# Debug.net
KiCad netlist of a schematic drawn in Altium Designer
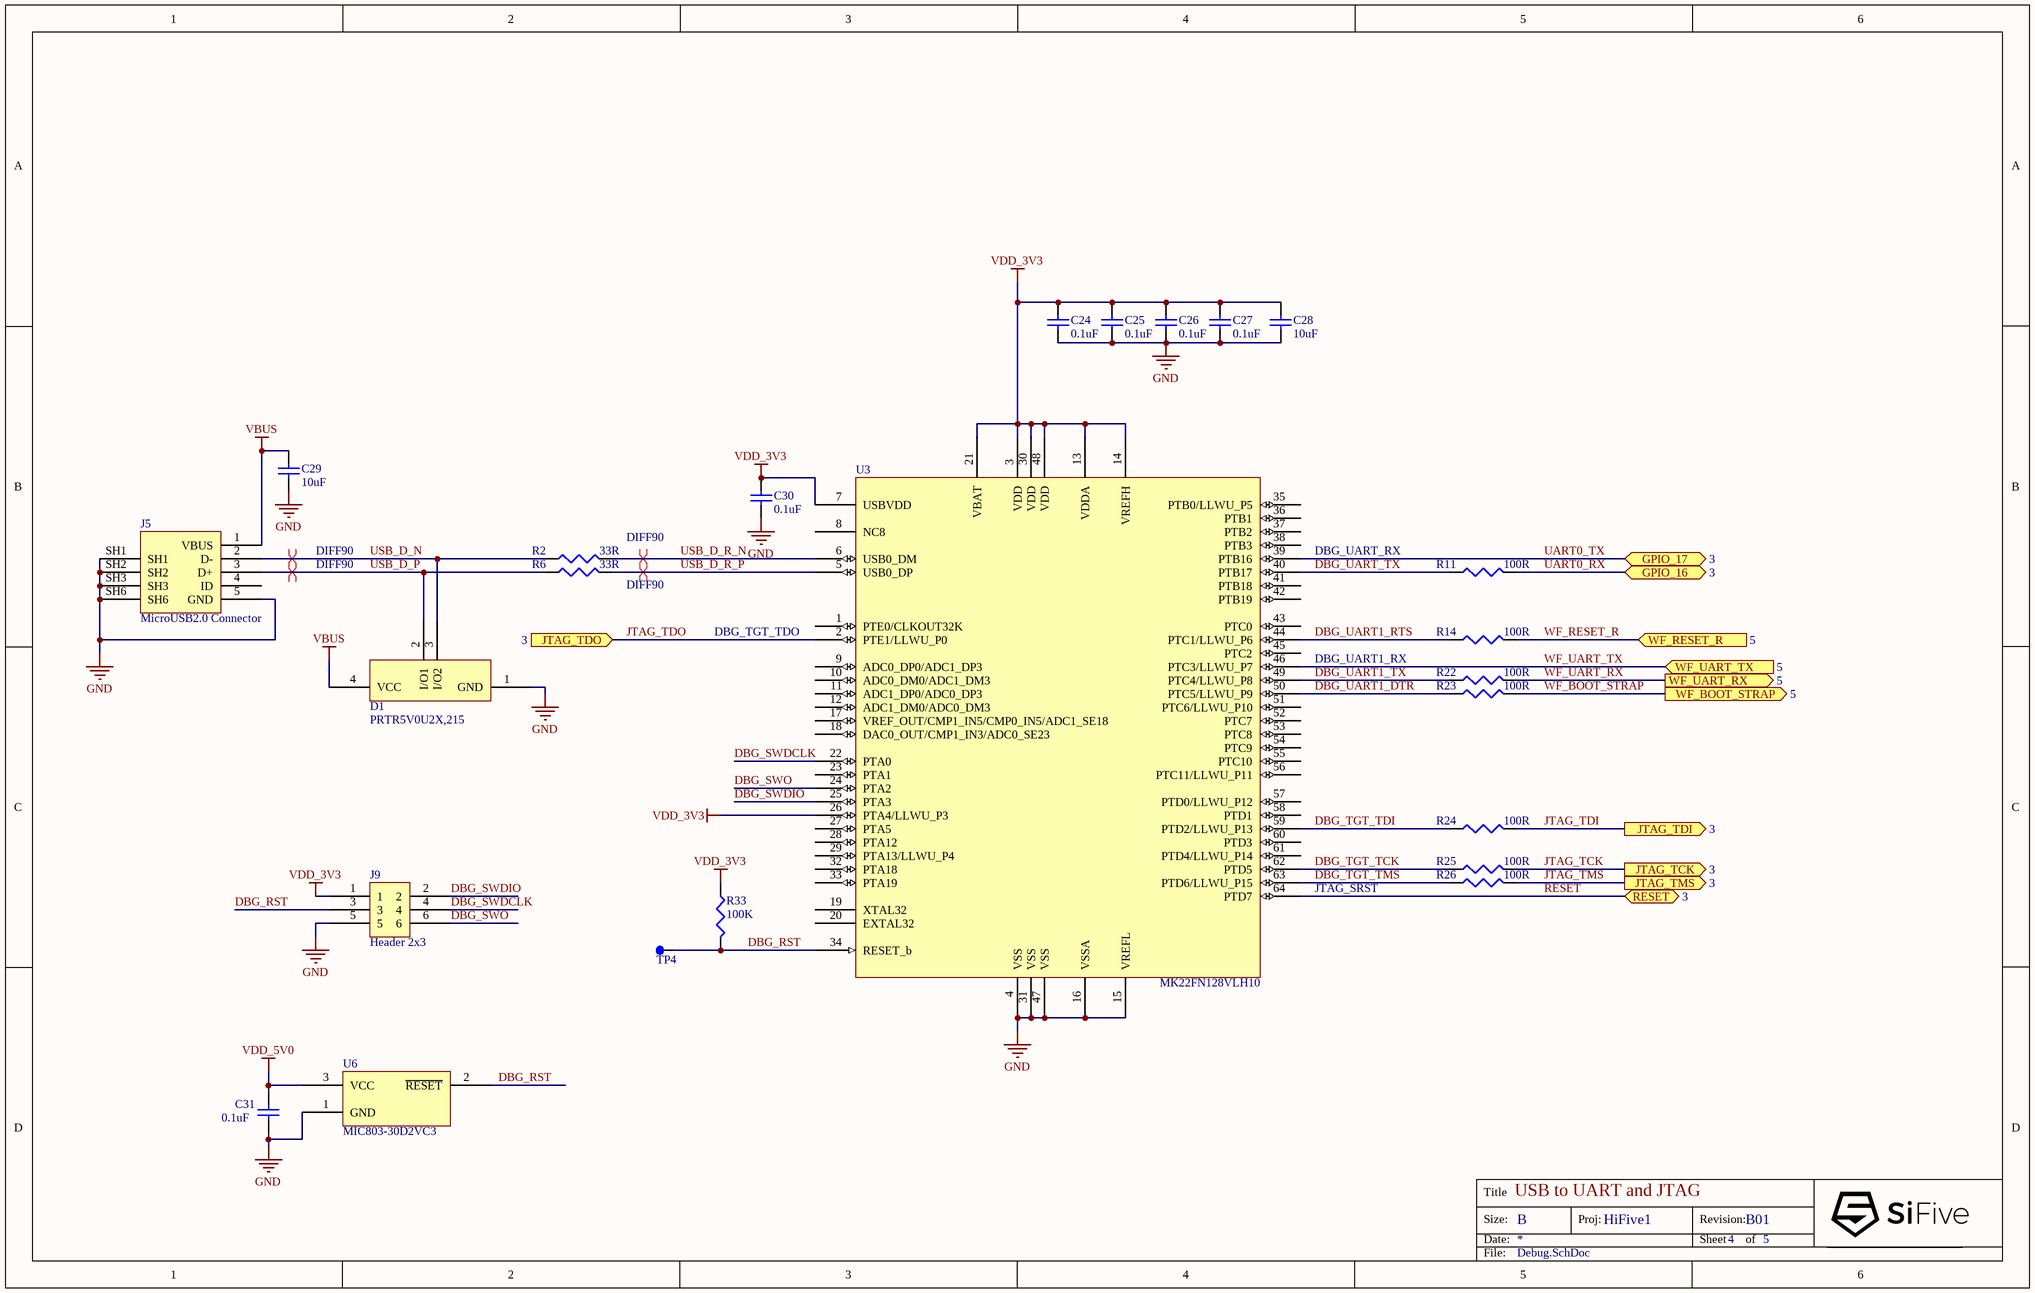
[diagram p0: Debug.SchDoc]

(export (version "E")
  (design (tool "Eeschema 10.0.6"))
  (components
    (comp (ref "C24")
      (value "0.1uF")
      (footprint "C0402")
      (description "0.10µF 16V Ceramic Capacitor X7R 0402")
      (fields
        (field (name "PART NUMBER") "C0100004")
        (field (name "MANUFACTURER") "Samsung Electro-Mechanics")
      )
      (libsource (lib "PartLibrary") (part "Capacitor - non polarized"))
    )
    (comp (ref "C25")
      (value "0.1uF")
      (footprint "C0402")
      (description "0.10µF 16V Ceramic Capacitor X7R 0402")
      (fields
        (field (name "PART NUMBER") "C0100004")
        (field (name "MANUFACTURER") "Samsung Electro-Mechanics")
      )
      (libsource (lib "PartLibrary") (part "Capacitor - non polarized"))
    )
    (comp (ref "C26")
      (value "0.1uF")
      (footprint "C0402")
      (description "0.10µF 16V Ceramic Capacitor X7R 0402")
      (fields
        (field (name "PART NUMBER") "C0100004")
        (field (name "MANUFACTURER") "Samsung Electro-Mechanics")
      )
      (libsource (lib "PartLibrary") (part "Capacitor - non polarized"))
    )
    (comp (ref "C27")
      (value "0.1uF")
      (footprint "C0402")
      (description "0.10µF 16V Ceramic Capacitor X7R 0402")
      (fields
        (field (name "PART NUMBER") "C0100004")
        (field (name "MANUFACTURER") "Samsung Electro-Mechanics")
      )
      (libsource (lib "PartLibrary") (part "Capacitor - non polarized"))
    )
    (comp (ref "C28")
      (value "10uF")
      (footprint "C0603")
      (description "CAP CER 10UF 10V X5R 0603")
      (fields (field (name "PART NUMBER") "C0100033") (field (name "MANUFACTURER") "Murata Electronics"))
      (libsource (lib "PartLibrary") (part "Capacitor - non polarized"))
    )
    (comp (ref "C29")
      (value "10uF")
      (footprint "C0603")
      (description "CAP CER 10UF 10V X5R 0603")
      (fields (field (name "PART NUMBER") "C0100033") (field (name "MANUFACTURER") "Murata Electronics"))
      (libsource (lib "PartLibrary") (part "Capacitor - non polarized"))
    )
    (comp (ref "C30")
      (value "0.1uF")
      (footprint "C0402")
      (description "0.10µF 16V Ceramic Capacitor X7R 0402")
      (fields
        (field (name "PART NUMBER") "C0100004")
        (field (name "MANUFACTURER") "Samsung Electro-Mechanics")
      )
      (libsource (lib "PartLibrary") (part "Capacitor - non polarized"))
    )
    (comp (ref "C31")
      (value "0.1uF")
      (footprint "C0402")
      (description "0.10µF 16V Ceramic Capacitor X7R 0402")
      (fields
        (field (name "PART NUMBER") "C0100004")
        (field (name "MANUFACTURER") "Samsung Electro-Mechanics")
      )
      (libsource (lib "PartLibrary") (part "Capacitor - non polarized"))
    )
    (comp (ref "D1")
      (value "PRTR5V0U2X,215")
      (footprint "SOT-143B")
      (description "TVS DIODE 5.5V SOT143B")
      (fields (field (name "PART NUMBER") "D0000012") (field (name "MANUFACTURER") "Nexperia"))
      (libsource (lib "PartLibrary") (part "PRTR5V0U2X_ESDDIODE"))
    )
    (comp (ref "J5")
      (value "MicroUSB2.0 Connector")
      (footprint "FCI_10118194-0001LF")
      (description "USB - micro B USB 2.0 Receptacle Connector 5 Position Surface Mount, Right Angle, Horizontal")
      (fields (field (name "PART NUMBER") "J0000048") (field (name "MANUFACTURER") "Amphenol FCI"))
      (libsource (lib "PartLibrary") (part "MicroUSB2.0 Connector"))
    )
    (comp (ref "J9")
      (value "Header 2x3")
      (footprint "TC2030-IDC-FP")
      (description "2x3 Connector, Small footprint, no legs, no component")
      (fields (field (name "PART NUMBER") "J0000045") (field (name "MANUFACTURER") "Tag Connect"))
      (libsource (lib "PartLibrary") (part "Header 2x3"))
    )
    (comp (ref "R2")
      (value "33R")
      (footprint "R0402")
      (description "RES SMD 33 OHM 1% 1/16W 0402")
      (fields (field (name "PART NUMBER") "R0000044") (field (name "MANUFACTURER") "Yageo"))
      (libsource (lib "PartLibrary") (part "Resistor"))
    )
    (comp (ref "R6")
      (value "33R")
      (footprint "R0402")
      (description "RES SMD 33 OHM 1% 1/16W 0402")
      (fields (field (name "PART NUMBER") "R0000044") (field (name "MANUFACTURER") "Yageo"))
      (libsource (lib "PartLibrary") (part "Resistor"))
    )
    (comp (ref "R11")
      (value "100R")
      (footprint "R0402")
      (description "RES SMD 100 OHM 1% 1/16W 0402")
      (fields (field (name "PART NUMBER") "R0000020") (field (name "MANUFACTURER") "Yageo"))
      (libsource (lib "PartLibrary") (part "Resistor"))
    )
    (comp (ref "R14")
      (value "100R")
      (footprint "R0402")
      (description "RES SMD 100 OHM 1% 1/16W 0402")
      (fields (field (name "PART NUMBER") "R0000020") (field (name "MANUFACTURER") "Yageo"))
      (libsource (lib "PartLibrary") (part "Resistor"))
    )
    (comp (ref "R22")
      (value "100R")
      (footprint "R0402")
      (description "RES SMD 100 OHM 1% 1/16W 0402")
      (fields (field (name "PART NUMBER") "R0000020") (field (name "MANUFACTURER") "Yageo"))
      (libsource (lib "PartLibrary") (part "Resistor"))
    )
    (comp (ref "R23")
      (value "100R")
      (footprint "R0402")
      (description "RES SMD 100 OHM 1% 1/16W 0402")
      (fields (field (name "PART NUMBER") "R0000020") (field (name "MANUFACTURER") "Yageo"))
      (libsource (lib "PartLibrary") (part "Resistor"))
    )
    (comp (ref "R24")
      (value "100R")
      (footprint "R0402")
      (description "RES SMD 100 OHM 1% 1/16W 0402")
      (fields (field (name "PART NUMBER") "R0000020") (field (name "MANUFACTURER") "Yageo"))
      (libsource (lib "PartLibrary") (part "Resistor"))
    )
    (comp (ref "R25")
      (value "100R")
      (footprint "R0402")
      (description "RES SMD 100 OHM 1% 1/16W 0402")
      (fields (field (name "PART NUMBER") "R0000020") (field (name "MANUFACTURER") "Yageo"))
      (libsource (lib "PartLibrary") (part "Resistor"))
    )
    (comp (ref "R26")
      (value "100R")
      (footprint "R0402")
      (description "RES SMD 100 OHM 1% 1/16W 0402")
      (fields (field (name "PART NUMBER") "R0000020") (field (name "MANUFACTURER") "Yageo"))
      (libsource (lib "PartLibrary") (part "Resistor"))
    )
    (comp (ref "R33")
      (value "100K")
      (footprint "R0402")
      (description "RES SMD 100K OHM 1% 1/16W 0402")
      (fields (field (name "PART NUMBER") "R0000012") (field (name "MANUFACTURER") "Yageo"))
      (libsource (lib "PartLibrary") (part "Resistor"))
    )
    (comp (ref "TP4")
      (value "Testpoint")
      (footprint "Testpoint_SMT")
      (description "Test Point SMT")
      (fields (field (name "PART NUMBER") "M0000002"))
      (libsource (lib "PartLibrary") (part "Testpoint"))
    )
    (comp (ref "U3")
      (value "MK22FN128VLH10")
      (footprint "LQFP-64")
      (fields (field (name "PART NUMBER") "U0000058") (field (name "MANUFACTURER") "NXP USA Inc"))
      (libsource (lib "PartLibrary") (part "MK22FN128VLH10"))
    )
    (comp (ref "U6")
      (value "MIC803-30D2VC3")
      (footprint "SOT65P210X110-3N_A")
      (description "IC MPU SUPERVISOR SC70-3")
      (fields (field (name "PART NUMBER") "U0000076") (field (name "MANUFACTURER") "Microchip"))
      (libsource (lib "PartLibrary") (part "MIC803-30D2VC3"))
    )
  )
  (nets
    (net (code "1") (name "/DBG_RST") (class "Default")
      (node (ref "J9") (pin "3") (pinfunction "3_3") (pintype "passive"))
      (node (ref "R33") (pin "2") (pinfunction "2_2") (pintype "passive"))
      (node (ref "TP4") (pin "1") (pinfunction "1_1") (pintype "passive"))
      (node (ref "U3") (pin "34") (pinfunction "RESET_b_34") (pintype "input"))
      (node (ref "U6") (pin "2") (pinfunction "~{RESET}_2") (pintype "open_collector"))
    )
    (net (code "2") (name "/DBG_SWDCLK") (class "Default")
      (node (ref "J9") (pin "4") (pinfunction "4_4") (pintype "passive"))
      (node (ref "U3") (pin "22") (pinfunction "PTA0_22") (pintype "bidirectional"))
    )
    (net (code "3") (name "/DBG_SWDIO") (class "Default")
      (node (ref "J9") (pin "2") (pinfunction "2_2") (pintype "passive"))
      (node (ref "U3") (pin "25") (pinfunction "PTA3_25") (pintype "bidirectional"))
    )
    (net (code "4") (name "/DBG_SWO") (class "Default")
      (node (ref "J9") (pin "6") (pinfunction "6_6") (pintype "passive"))
      (node (ref "U3") (pin "24") (pinfunction "PTA2_24") (pintype "bidirectional"))
    )
    (net (code "5") (name "/DBG_TGT_TCK") (class "Default")
      (node (ref "R25") (pin "1") (pinfunction "1_1") (pintype "passive"))
      (node (ref "U3") (pin "62") (pinfunction "PTD5_62") (pintype "bidirectional"))
    )
    (net (code "6") (name "/DBG_TGT_TDI") (class "Default")
      (node (ref "R24") (pin "1") (pinfunction "1_1") (pintype "passive"))
      (node (ref "U3") (pin "59") (pinfunction "PTD2/LLWU_P13_59") (pintype "bidirectional"))
    )
    (net (code "7") (name "/DBG_TGT_TMS") (class "Default")
      (node (ref "R26") (pin "1") (pinfunction "1_1") (pintype "passive"))
      (node (ref "U3") (pin "63") (pinfunction "PTD6/LLWU_P15_63") (pintype "bidirectional"))
    )
    (net (code "8") (name "/DBG_UART1_DTR") (class "Default")
      (node (ref "R23") (pin "1") (pinfunction "1_1") (pintype "passive"))
      (node (ref "U3") (pin "50") (pinfunction "PTC5/LLWU_P9_50") (pintype "bidirectional"))
    )
    (net (code "9") (name "/DBG_UART1_RTS") (class "Default")
      (node (ref "R14") (pin "1") (pinfunction "1_1") (pintype "passive"))
      (node (ref "U3") (pin "44") (pinfunction "PTC1/LLWU_P6_44") (pintype "bidirectional"))
    )
    (net (code "10") (name "/DBG_UART1_TX") (class "Default")
      (node (ref "R22") (pin "1") (pinfunction "1_1") (pintype "passive"))
      (node (ref "U3") (pin "49") (pinfunction "PTC4/LLWU_P8_49") (pintype "bidirectional"))
    )
    (net (code "11") (name "/DBG_UART_TX") (class "Default")
      (node (ref "R11") (pin "1") (pinfunction "1_1") (pintype "passive"))
      (node (ref "U3") (pin "40") (pinfunction "PTB17_40") (pintype "bidirectional"))
    )
    (net (code "12") (name "/JTAG_TCK") (class "Default")
      (node (ref "R25") (pin "2") (pinfunction "2_2") (pintype "passive"))
    )
    (net (code "13") (name "/JTAG_TDI") (class "Default")
      (node (ref "R24") (pin "2") (pinfunction "2_2") (pintype "passive"))
    )
    (net (code "14") (name "/JTAG_TDO") (class "Default")
      (node (ref "U3") (pin "2") (pinfunction "PTE1/LLWU_P0_2") (pintype "bidirectional"))
    )
    (net (code "15") (name "/JTAG_TMS") (class "Default")
      (node (ref "R26") (pin "2") (pinfunction "2_2") (pintype "passive"))
    )
    (net (code "16") (name "/RESET") (class "Default")
      (node (ref "U3") (pin "64") (pinfunction "PTD7_64") (pintype "bidirectional"))
    )
    (net (code "17") (name "/UART0_RX") (class "Default")
      (node (ref "R11") (pin "2") (pinfunction "2_2") (pintype "passive"))
    )
    (net (code "18") (name "/UART0_TX") (class "Default")
      (node (ref "U3") (pin "39") (pinfunction "PTB16_39") (pintype "bidirectional"))
    )
    (net (code "19") (name "/USB_D_N") (class "Default")
      (node (ref "D1") (pin "3") (pinfunction "I/O2_3") (pintype "passive"))
      (node (ref "J5") (pin "2") (pinfunction "D-_2") (pintype "passive"))
      (node (ref "R2") (pin "1") (pinfunction "1_1") (pintype "passive"))
    )
    (net (code "20") (name "/USB_D_P") (class "Default")
      (node (ref "D1") (pin "2") (pinfunction "I/O1_2") (pintype "passive"))
      (node (ref "J5") (pin "3") (pinfunction "D+_3") (pintype "passive"))
      (node (ref "R6") (pin "1") (pinfunction "1_1") (pintype "passive"))
    )
    (net (code "21") (name "/USB_D_R_N") (class "Default")
      (node (ref "R2") (pin "2") (pinfunction "2_2") (pintype "passive"))
      (node (ref "U3") (pin "6") (pinfunction "USB0_DM_6") (pintype "bidirectional"))
    )
    (net (code "22") (name "/USB_D_R_P") (class "Default")
      (node (ref "R6") (pin "2") (pinfunction "2_2") (pintype "passive"))
      (node (ref "U3") (pin "5") (pinfunction "USB0_DP_5") (pintype "bidirectional"))
    )
    (net (code "23") (name "/WF_BOOT_STRAP") (class "Default")
      (node (ref "R23") (pin "2") (pinfunction "2_2") (pintype "passive"))
    )
    (net (code "24") (name "/WF_RESET_R") (class "Default")
      (node (ref "R14") (pin "2") (pinfunction "2_2") (pintype "passive"))
    )
    (net (code "25") (name "/WF_UART_RX") (class "Default")
      (node (ref "R22") (pin "2") (pinfunction "2_2") (pintype "passive"))
    )
    (net (code "26") (name "/WF_UART_TX") (class "Default")
      (node (ref "U3") (pin "46") (pinfunction "PTC3/LLWU_P7_46") (pintype "bidirectional"))
    )
    (net (code "27") (name "GND") (class "Default")
      (node (ref "C24") (pin "2") (pinfunction "2_2") (pintype "passive"))
      (node (ref "C25") (pin "2") (pinfunction "2_2") (pintype "passive"))
      (node (ref "C26") (pin "2") (pinfunction "2_2") (pintype "passive"))
      (node (ref "C27") (pin "2") (pinfunction "2_2") (pintype "passive"))
      (node (ref "C28") (pin "1") (pinfunction "1_1") (pintype "passive"))
      (node (ref "C29") (pin "1") (pinfunction "1_1") (pintype "passive"))
      (node (ref "C30") (pin "2") (pinfunction "2_2") (pintype "passive"))
      (node (ref "C31") (pin "2") (pinfunction "2_2") (pintype "passive"))
      (node (ref "D1") (pin "1") (pinfunction "GND_1") (pintype "power_in"))
      (node (ref "J5") (pin "5") (pinfunction "GND_5") (pintype "passive"))
      (node (ref "J5") (pin "SH1") (pinfunction "SH1_SH1") (pintype "passive"))
      (node (ref "J5") (pin "SH2") (pinfunction "SH2_SH2") (pintype "passive"))
      (node (ref "J5") (pin "SH3") (pinfunction "SH3_SH3") (pintype "passive"))
      (node (ref "J5") (pin "SH6") (pinfunction "SH6_SH6") (pintype "passive"))
      (node (ref "J9") (pin "5") (pinfunction "5_5") (pintype "passive"))
      (node (ref "U3") (pin "15") (pinfunction "VREFL_15") (pintype "passive"))
      (node (ref "U3") (pin "16") (pinfunction "VSSA_16") (pintype "passive"))
      (node (ref "U3") (pin "31") (pinfunction "VSS_31") (pintype "passive"))
      (node (ref "U3") (pin "4") (pinfunction "VSS_4") (pintype "passive"))
      (node (ref "U3") (pin "47") (pinfunction "VSS_47") (pintype "passive"))
      (node (ref "U6") (pin "1") (pinfunction "GND_1") (pintype "power_in"))
    )
    (net (code "28") (name "VBUS") (class "Default")
      (node (ref "C29") (pin "2") (pinfunction "2_2") (pintype "passive"))
      (node (ref "D1") (pin "4") (pinfunction "VCC_4") (pintype "power_in"))
      (node (ref "J5") (pin "1") (pinfunction "VBUS_1") (pintype "passive"))
    )
    (net (code "29") (name "VDD_3V3") (class "Default")
      (node (ref "C24") (pin "1") (pinfunction "1_1") (pintype "passive"))
      (node (ref "C25") (pin "1") (pinfunction "1_1") (pintype "passive"))
      (node (ref "C26") (pin "1") (pinfunction "1_1") (pintype "passive"))
      (node (ref "C27") (pin "1") (pinfunction "1_1") (pintype "passive"))
      (node (ref "C28") (pin "2") (pinfunction "2_2") (pintype "passive"))
      (node (ref "C30") (pin "1") (pinfunction "1_1") (pintype "passive"))
      (node (ref "J9") (pin "1") (pinfunction "1_1") (pintype "passive"))
      (node (ref "R33") (pin "1") (pinfunction "1_1") (pintype "passive"))
      (node (ref "U3") (pin "13") (pinfunction "VDDA_13") (pintype "power_in"))
      (node (ref "U3") (pin "14") (pinfunction "VREFH_14") (pintype "passive"))
      (node (ref "U3") (pin "21") (pinfunction "VBAT_21") (pintype "power_in"))
      (node (ref "U3") (pin "26") (pinfunction "PTA4/LLWU_P3_26") (pintype "bidirectional"))
      (node (ref "U3") (pin "3") (pinfunction "VDD_3") (pintype "power_in"))
      (node (ref "U3") (pin "30") (pinfunction "VDD_30") (pintype "power_in"))
      (node (ref "U3") (pin "48") (pinfunction "VDD_48") (pintype "power_in"))
      (node (ref "U3") (pin "7") (pinfunction "USBVDD_7") (pintype "power_in"))
    )
    (net (code "30") (name "VDD_5V0") (class "Default")
      (node (ref "C31") (pin "1") (pinfunction "1_1") (pintype "passive"))
      (node (ref "U6") (pin "3") (pinfunction "VCC_3") (pintype "power_in"))
    )
    (net (code "31") (name "unconnected-(J5-ID-Pad4)") (class "Default")
      (node (ref "J5") (pin "4") (pinfunction "ID_4") (pintype "passive"))
    )
    (net (code "32") (name "unconnected-(U3-ADC0_DM0{slash}ADC1_DM3-Pad10)") (class "Default")
      (node (ref "U3") (pin "10") (pinfunction "ADC0_DM0/ADC1_DM3_10") (pintype "bidirectional"))
    )
    (net (code "33") (name "unconnected-(U3-ADC0_DP0{slash}ADC1_DP3-Pad9)") (class "Default")
      (node (ref "U3") (pin "9") (pinfunction "ADC0_DP0/ADC1_DP3_9") (pintype "bidirectional"))
    )
    (net (code "34") (name "unconnected-(U3-ADC1_DM0{slash}ADC0_DM3-Pad12)") (class "Default")
      (node (ref "U3") (pin "12") (pinfunction "ADC1_DM0/ADC0_DM3_12") (pintype "bidirectional"))
    )
    (net (code "35") (name "unconnected-(U3-ADC1_DP0{slash}ADC0_DP3-Pad11)") (class "Default")
      (node (ref "U3") (pin "11") (pinfunction "ADC1_DP0/ADC0_DP3_11") (pintype "bidirectional"))
    )
    (net (code "36") (name "unconnected-(U3-DAC0_OUT{slash}CMP1_IN3{slash}ADC0_SE23-Pad18)") (class "Default")
      (node (ref "U3") (pin "18") (pinfunction "DAC0_OUT/CMP1_IN3/ADC0_SE23_18") (pintype "bidirectional"))
    )
    (net (code "37") (name "unconnected-(U3-EXTAL32-Pad20)") (class "Default")
      (node (ref "U3") (pin "20") (pinfunction "EXTAL32_20") (pintype "passive"))
    )
    (net (code "38") (name "unconnected-(U3-NC8-Pad8)") (class "Default")
      (node (ref "U3") (pin "8") (pinfunction "NC8_8") (pintype "passive"))
    )
    (net (code "39") (name "unconnected-(U3-PTA1-Pad23)") (class "Default")
      (node (ref "U3") (pin "23") (pinfunction "PTA1_23") (pintype "bidirectional"))
    )
    (net (code "40") (name "unconnected-(U3-PTA5-Pad27)") (class "Default")
      (node (ref "U3") (pin "27") (pinfunction "PTA5_27") (pintype "bidirectional"))
    )
    (net (code "41") (name "unconnected-(U3-PTA12-Pad28)") (class "Default")
      (node (ref "U3") (pin "28") (pinfunction "PTA12_28") (pintype "bidirectional"))
    )
    (net (code "42") (name "unconnected-(U3-PTA13{slash}LLWU_P4-Pad29)") (class "Default")
      (node (ref "U3") (pin "29") (pinfunction "PTA13/LLWU_P4_29") (pintype "bidirectional"))
    )
    (net (code "43") (name "unconnected-(U3-PTA18-Pad32)") (class "Default")
      (node (ref "U3") (pin "32") (pinfunction "PTA18_32") (pintype "bidirectional"))
    )
    (net (code "44") (name "unconnected-(U3-PTA19-Pad33)") (class "Default")
      (node (ref "U3") (pin "33") (pinfunction "PTA19_33") (pintype "bidirectional"))
    )
    (net (code "45") (name "unconnected-(U3-PTB0{slash}LLWU_P5-Pad35)") (class "Default")
      (node (ref "U3") (pin "35") (pinfunction "PTB0/LLWU_P5_35") (pintype "bidirectional"))
    )
    (net (code "46") (name "unconnected-(U3-PTB1-Pad36)") (class "Default")
      (node (ref "U3") (pin "36") (pinfunction "PTB1_36") (pintype "bidirectional"))
    )
    (net (code "47") (name "unconnected-(U3-PTB2-Pad37)") (class "Default")
      (node (ref "U3") (pin "37") (pinfunction "PTB2_37") (pintype "bidirectional"))
    )
    (net (code "48") (name "unconnected-(U3-PTB3-Pad38)") (class "Default")
      (node (ref "U3") (pin "38") (pinfunction "PTB3_38") (pintype "bidirectional"))
    )
    (net (code "49") (name "unconnected-(U3-PTB18-Pad41)") (class "Default")
      (node (ref "U3") (pin "41") (pinfunction "PTB18_41") (pintype "bidirectional"))
    )
    (net (code "50") (name "unconnected-(U3-PTB19-Pad42)") (class "Default")
      (node (ref "U3") (pin "42") (pinfunction "PTB19_42") (pintype "bidirectional"))
    )
    (net (code "51") (name "unconnected-(U3-PTC0-Pad43)") (class "Default")
      (node (ref "U3") (pin "43") (pinfunction "PTC0_43") (pintype "bidirectional"))
    )
    (net (code "52") (name "unconnected-(U3-PTC2-Pad45)") (class "Default")
      (node (ref "U3") (pin "45") (pinfunction "PTC2_45") (pintype "bidirectional"))
    )
    (net (code "53") (name "unconnected-(U3-PTC6{slash}LLWU_P10-Pad51)") (class "Default")
      (node (ref "U3") (pin "51") (pinfunction "PTC6/LLWU_P10_51") (pintype "bidirectional"))
    )
    (net (code "54") (name "unconnected-(U3-PTC7-Pad52)") (class "Default")
      (node (ref "U3") (pin "52") (pinfunction "PTC7_52") (pintype "bidirectional"))
    )
    (net (code "55") (name "unconnected-(U3-PTC8-Pad53)") (class "Default")
      (node (ref "U3") (pin "53") (pinfunction "PTC8_53") (pintype "bidirectional"))
    )
    (net (code "56") (name "unconnected-(U3-PTC9-Pad54)") (class "Default")
      (node (ref "U3") (pin "54") (pinfunction "PTC9_54") (pintype "bidirectional"))
    )
    (net (code "57") (name "unconnected-(U3-PTC10-Pad55)") (class "Default")
      (node (ref "U3") (pin "55") (pinfunction "PTC10_55") (pintype "bidirectional"))
    )
    (net (code "58") (name "unconnected-(U3-PTC11{slash}LLWU_P11-Pad56)") (class "Default")
      (node (ref "U3") (pin "56") (pinfunction "PTC11/LLWU_P11_56") (pintype "bidirectional"))
    )
    (net (code "59") (name "unconnected-(U3-PTD0{slash}LLWU_P12-Pad57)") (class "Default")
      (node (ref "U3") (pin "57") (pinfunction "PTD0/LLWU_P12_57") (pintype "bidirectional"))
    )
    (net (code "60") (name "unconnected-(U3-PTD1-Pad58)") (class "Default")
      (node (ref "U3") (pin "58") (pinfunction "PTD1_58") (pintype "bidirectional"))
    )
    (net (code "61") (name "unconnected-(U3-PTD3-Pad60)") (class "Default")
      (node (ref "U3") (pin "60") (pinfunction "PTD3_60") (pintype "bidirectional"))
    )
    (net (code "62") (name "unconnected-(U3-PTD4{slash}LLWU_P14-Pad61)") (class "Default")
      (node (ref "U3") (pin "61") (pinfunction "PTD4/LLWU_P14_61") (pintype "bidirectional"))
    )
    (net (code "63") (name "unconnected-(U3-PTE0{slash}CLKOUT32K-Pad1)") (class "Default")
      (node (ref "U3") (pin "1") (pinfunction "PTE0/CLKOUT32K_1") (pintype "bidirectional"))
    )
    (net (code "64") (name "unconnected-(U3-VREF_OUT{slash}CMP1_IN5{slash}CMP0_IN5{slash}ADC1_SE18-Pad17)") (class "Default")
      (node (ref "U3") (pin "17") (pinfunction "VREF_OUT/CMP1_IN5/CMP0_IN5/ADC1_SE18_17") (pintype "bidirectional"))
    )
    (net (code "65") (name "unconnected-(U3-XTAL32-Pad19)") (class "Default")
      (node (ref "U3") (pin "19") (pinfunction "XTAL32_19") (pintype "passive"))
    )
  )
)
